# Core_h750vb.net
KiCad netlist of a schematic drawn in Altium Designer
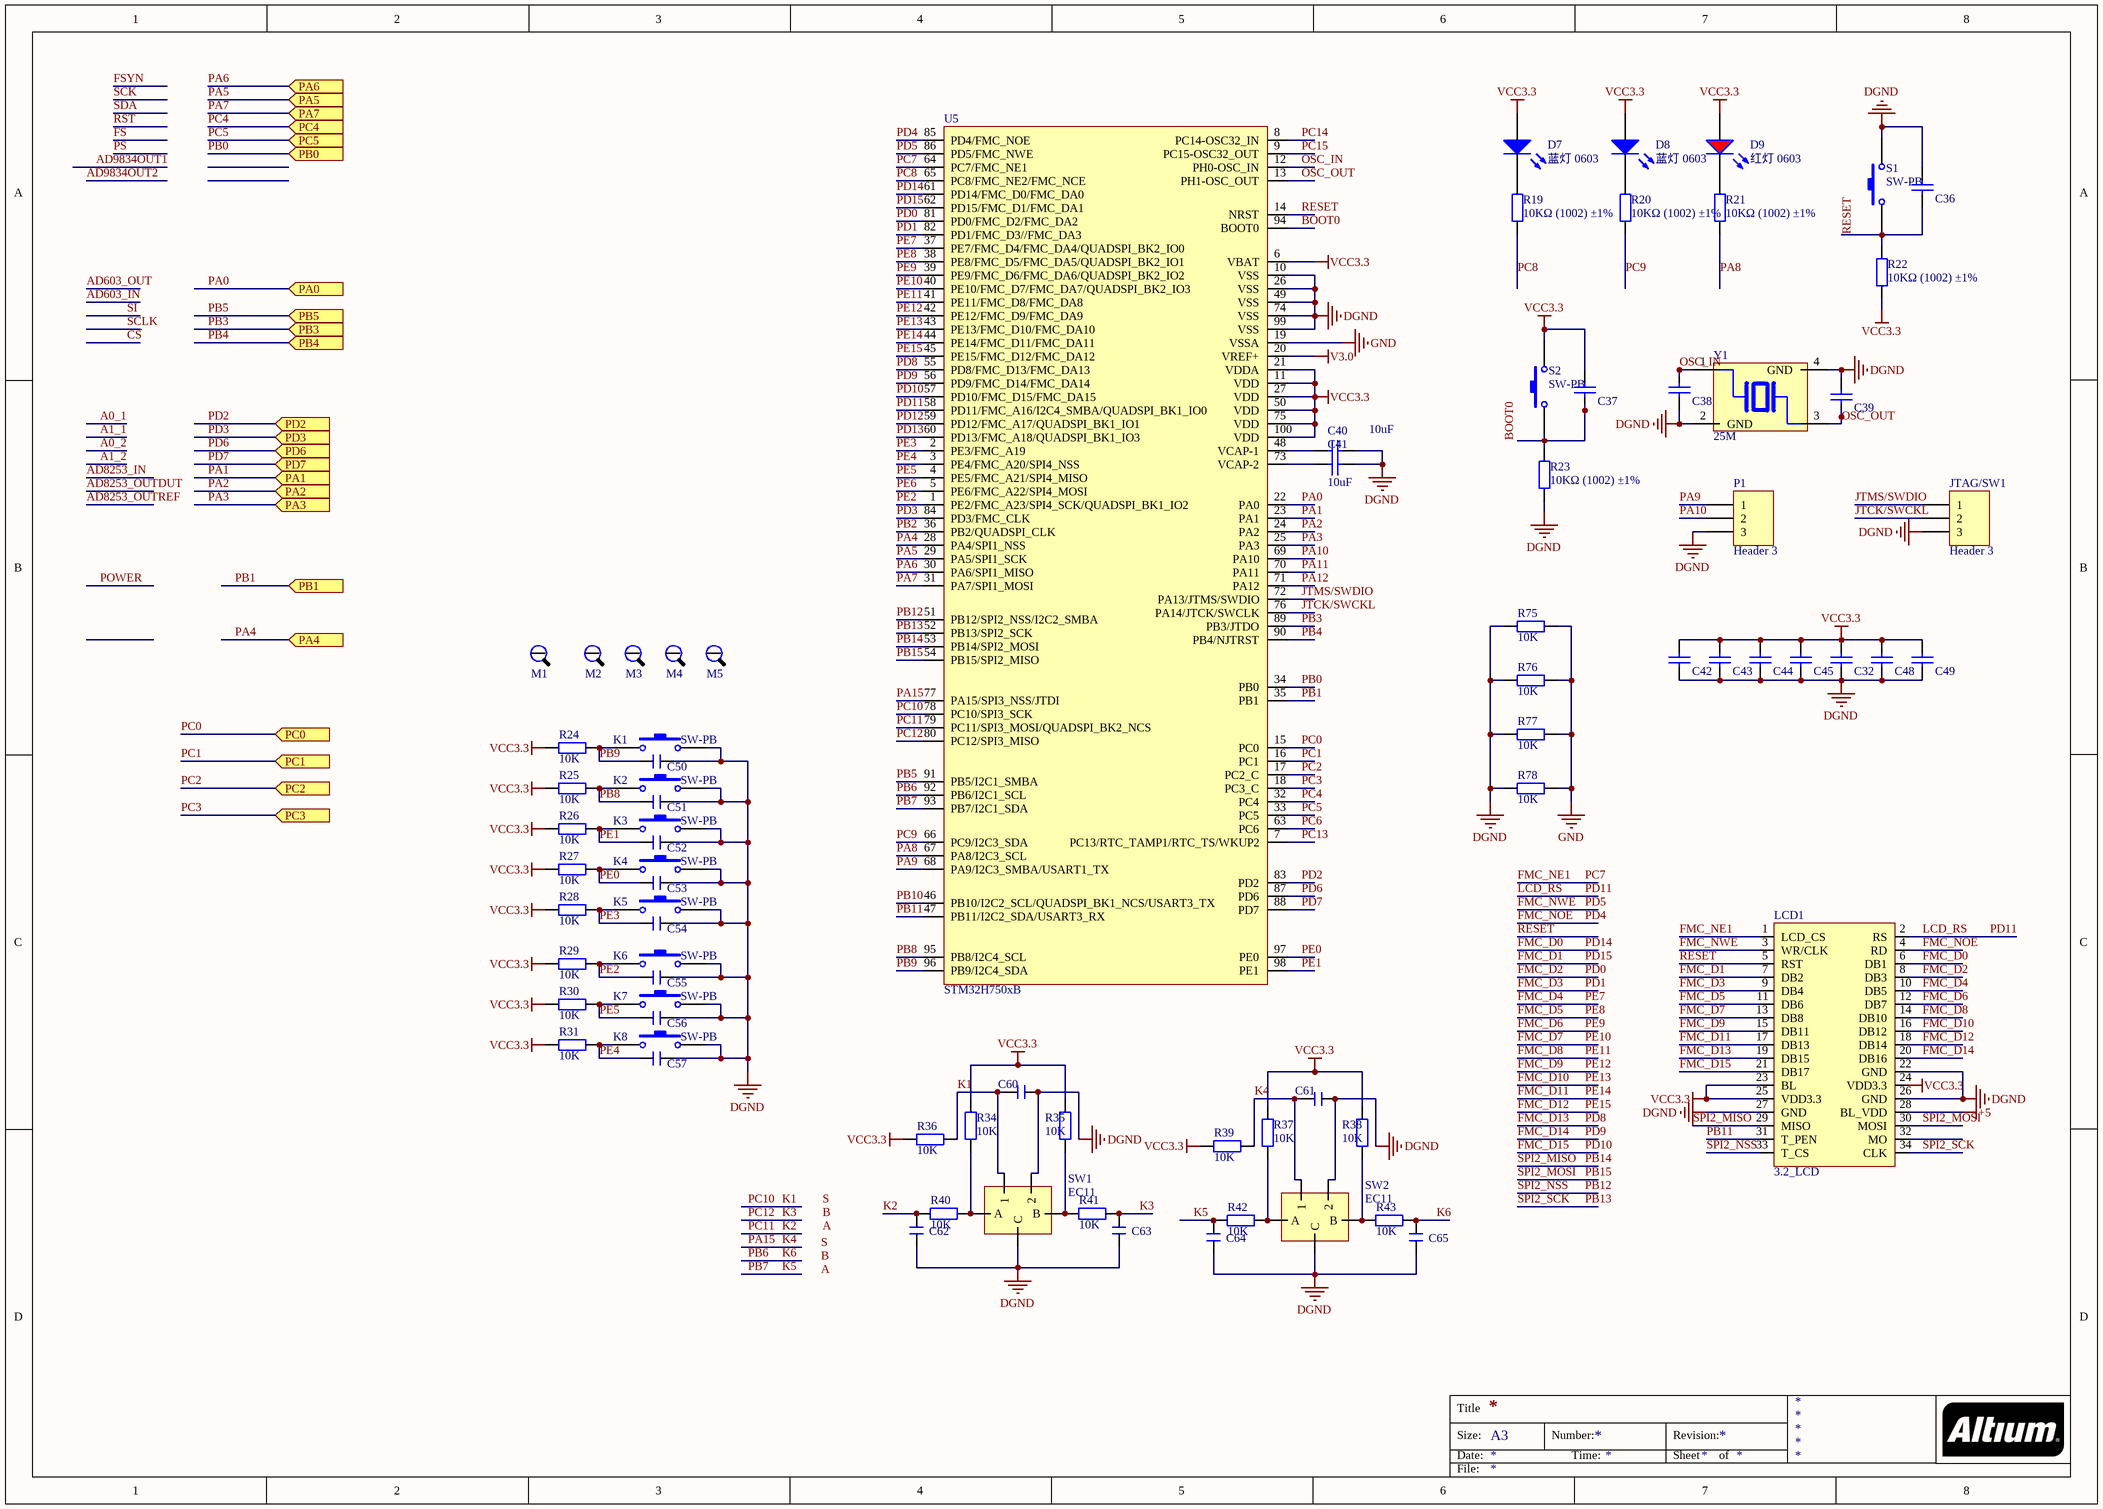
[diagram p0: Core_h750vb.SchDoc]

(export (version "E")
  (design (tool "Eeschema 10.0.6"))
  (components
    (comp (ref "C32")
      (value "100nF (104) 10% 50V")
      (footprint "0603_C")
      (description "贴片电容")
      (libsource (lib "JLC") (part "0603 100nF (104) 10% 50V"))
    )
    (comp (ref "C36")
      (value "100nF (104) 10% 50V")
      (footprint "0603_C")
      (description "贴片电容")
      (libsource (lib "JLC") (part "0603 100nF (104) 10% 50V"))
    )
    (comp (ref "C37")
      (value "100nF (104) 10% 50V")
      (footprint "0603_C")
      (description "贴片电容")
      (libsource (lib "JLC") (part "0603 100nF (104) 10% 50V"))
    )
    (comp (ref "C38")
      (value "100nF (104) 10% 50V")
      (footprint "0603_C")
      (description "贴片电容")
      (libsource (lib "JLC") (part "0603 100nF (104) 10% 50V"))
    )
    (comp (ref "C39")
      (value "100nF (104) 10% 50V")
      (footprint "0603_C")
      (description "贴片电容")
      (libsource (lib "JLC") (part "0603 100nF (104) 10% 50V"))
    )
    (comp (ref "C40")
      (value "10uF")
      (footprint "0603_C")
      (description "贴片电容")
      (libsource (lib "JLC") (part "0603 10uF (106) 10% 10V"))
    )
    (comp (ref "C41")
      (value "10uF")
      (footprint "0603_C")
      (description "贴片电容")
      (libsource (lib "JLC") (part "0603 10uF (106) 10% 10V"))
    )
    (comp (ref "C42")
      (value "100nF (104) 10% 50V")
      (footprint "0603_C")
      (description "贴片电容")
      (libsource (lib "JLC") (part "0603 100nF (104) 10% 50V"))
    )
    (comp (ref "C43")
      (value "100nF (104) 10% 50V")
      (footprint "0603_C")
      (description "贴片电容")
      (libsource (lib "JLC") (part "0603 100nF (104) 10% 50V"))
    )
    (comp (ref "C44")
      (value "100nF (104) 10% 50V")
      (footprint "0603_C")
      (description "贴片电容")
      (libsource (lib "JLC") (part "0603 100nF (104) 10% 50V"))
    )
    (comp (ref "C45")
      (value "100nF (104) 10% 50V")
      (footprint "0603_C")
      (description "贴片电容")
      (libsource (lib "JLC") (part "0603 100nF (104) 10% 50V"))
    )
    (comp (ref "C48")
      (value "100nF (104) 10% 50V")
      (footprint "0603_C")
      (description "贴片电容")
      (libsource (lib "JLC") (part "0603 100nF (104) 10% 50V"))
    )
    (comp (ref "C49")
      (value "100nF (104) 10% 50V")
      (footprint "0603_C")
      (description "贴片电容")
      (libsource (lib "JLC") (part "0603 100nF (104) 10% 50V"))
    )
    (comp (ref "C50")
      (value "104")
      (footprint "0603_C")
      (description "无极性贴片电容")
      (libsource (lib "各类封装") (part "C"))
    )
    (comp (ref "C51")
      (value "104")
      (footprint "0603_C")
      (description "无极性贴片电容")
      (libsource (lib "各类封装") (part "C"))
    )
    (comp (ref "C52")
      (value "104")
      (footprint "0603_C")
      (description "无极性贴片电容")
      (libsource (lib "各类封装") (part "C"))
    )
    (comp (ref "C53")
      (value "104")
      (footprint "0603_C")
      (description "无极性贴片电容")
      (libsource (lib "各类封装") (part "C"))
    )
    (comp (ref "C54")
      (value "104")
      (footprint "0603_C")
      (description "无极性贴片电容")
      (libsource (lib "各类封装") (part "C"))
    )
    (comp (ref "C55")
      (value "104")
      (footprint "0603_C")
      (description "无极性贴片电容")
      (libsource (lib "各类封装") (part "C"))
    )
    (comp (ref "C56")
      (value "104")
      (footprint "0603_C")
      (description "无极性贴片电容")
      (libsource (lib "各类封装") (part "C"))
    )
    (comp (ref "C57")
      (value "104")
      (footprint "0603_C")
      (description "无极性贴片电容")
      (libsource (lib "各类封装") (part "C"))
    )
    (comp (ref "C60")
      (value "104")
      (footprint "0603_C")
      (description "无极性贴片电容")
      (libsource (lib "各类封装") (part "C"))
    )
    (comp (ref "C61")
      (value "104")
      (footprint "0603_C")
      (description "无极性贴片电容")
      (libsource (lib "各类封装") (part "C"))
    )
    (comp (ref "C62")
      (value "104")
      (footprint "0603_C")
      (description "无极性贴片电容")
      (libsource (lib "各类封装") (part "C"))
    )
    (comp (ref "C63")
      (value "104")
      (footprint "0603_C")
      (description "无极性贴片电容")
      (libsource (lib "各类封装") (part "C"))
    )
    (comp (ref "C64")
      (value "104")
      (footprint "0603_C")
      (description "无极性贴片电容")
      (libsource (lib "各类封装") (part "C"))
    )
    (comp (ref "C65")
      (value "104")
      (footprint "0603_C")
      (description "无极性贴片电容")
      (libsource (lib "各类封装") (part "C"))
    )
    (comp (ref "D7")
      (value "蓝灯 0603")
      (footprint "0603_LED_S1")
      (description "发光二极管")
      (libsource (lib "JLC") (part "0603 蓝灯"))
    )
    (comp (ref "D8")
      (value "蓝灯 0603")
      (footprint "0603_LED_S1")
      (description "发光二极管")
      (libsource (lib "JLC") (part "0603 蓝灯"))
    )
    (comp (ref "D9")
      (value "红灯 0603")
      (footprint "0603_LED_S1")
      (description "发光二极管")
      (libsource (lib "JLC") (part "0603 红灯"))
    )
    (comp (ref "JTAG/SW1")
      (value "Header 3")
      (footprint "HDR1X3")
      (description "Header, 3-Pin")
      (fields (field (name "PUBLISHER") "Altium Limited"))
      (libsource (lib "Miscellaneous Connectors") (part "Header 3"))
    )
    (comp (ref "K1")
      (value "SW-PB")
      (footprint "SW_PB2_A1")
      (description "微动开关")
      (fields (field (name "PUBLISHER") "Altium Limited"))
      (libsource (lib "主集成库") (part "SW-PB"))
    )
    (comp (ref "K2")
      (value "SW-PB")
      (footprint "SW_PB2_A1")
      (description "微动开关")
      (fields (field (name "PUBLISHER") "Altium Limited"))
      (libsource (lib "主集成库") (part "SW-PB"))
    )
    (comp (ref "K3")
      (value "SW-PB")
      (footprint "SW_PB2_A1")
      (description "微动开关")
      (fields (field (name "PUBLISHER") "Altium Limited"))
      (libsource (lib "主集成库") (part "SW-PB"))
    )
    (comp (ref "K4")
      (value "SW-PB")
      (footprint "SW_PB2_A1")
      (description "微动开关")
      (fields (field (name "PUBLISHER") "Altium Limited"))
      (libsource (lib "主集成库") (part "SW-PB"))
    )
    (comp (ref "K5")
      (value "SW-PB")
      (footprint "SW_PB2_A1")
      (description "微动开关")
      (fields (field (name "PUBLISHER") "Altium Limited"))
      (libsource (lib "主集成库") (part "SW-PB"))
    )
    (comp (ref "K6")
      (value "SW-PB")
      (footprint "SW_PB2_A1")
      (description "微动开关")
      (fields (field (name "PUBLISHER") "Altium Limited"))
      (libsource (lib "主集成库") (part "SW-PB"))
    )
    (comp (ref "K7")
      (value "SW-PB")
      (footprint "SW_PB2_A1")
      (description "微动开关")
      (fields (field (name "PUBLISHER") "Altium Limited"))
      (libsource (lib "主集成库") (part "SW-PB"))
    )
    (comp (ref "K8")
      (value "SW-PB")
      (footprint "SW_PB2_A1")
      (description "微动开关")
      (fields (field (name "PUBLISHER") "Altium Limited"))
      (libsource (lib "主集成库") (part "SW-PB"))
    )
    (comp (ref "LCD1") (value "3.2_LCD") (footprint "LCD_3.2") (libsource (lib "直流电源") (part "3.2_LCD")))
    (comp (ref "M1")
      (value "M3")
      (footprint "M3x10_L")
      (description "螺丝")
      (libsource (lib "Cooperation") (part "ELSE_M3_screw"))
    )
    (comp (ref "M2")
      (value "M3")
      (footprint "M3x10_L")
      (description "螺丝")
      (libsource (lib "Cooperation") (part "ELSE_M3_screw"))
    )
    (comp (ref "M3")
      (value "M3")
      (footprint "M3x10_L")
      (description "螺丝")
      (libsource (lib "Cooperation") (part "ELSE_M3_screw"))
    )
    (comp (ref "M4")
      (value "M3")
      (footprint "M3x10_L")
      (description "螺丝")
      (libsource (lib "Cooperation") (part "ELSE_M3_screw"))
    )
    (comp (ref "M5")
      (value "M3")
      (footprint "M3x10_L")
      (description "螺丝")
      (libsource (lib "Cooperation") (part "ELSE_M3_screw"))
    )
    (comp (ref "P1")
      (value "Header 3")
      (footprint "HDR1X3")
      (description "Header, 3-Pin")
      (fields (field (name "PUBLISHER") "Altium Limited"))
      (libsource (lib "Miscellaneous Connectors") (part "Header 3"))
    )
    (comp (ref "R19")
      (value "10KΩ (1002) ±1%")
      (footprint "0603_R")
      (description "贴片电阻")
      (libsource (lib "JLC") (part "0603 10KΩ (1002) 1%"))
    )
    (comp (ref "R20")
      (value "10KΩ (1002) ±1%")
      (footprint "0603_R")
      (description "贴片电阻")
      (libsource (lib "JLC") (part "0603 10KΩ (1002) 1%"))
    )
    (comp (ref "R21")
      (value "10KΩ (1002) ±1%")
      (footprint "0603_R")
      (description "贴片电阻")
      (libsource (lib "JLC") (part "0603 10KΩ (1002) 1%"))
    )
    (comp (ref "R22")
      (value "10KΩ (1002) ±1%")
      (footprint "0603_R")
      (description "贴片电阻")
      (libsource (lib "JLC") (part "0603 10KΩ (1002) 1%"))
    )
    (comp (ref "R23")
      (value "10KΩ (1002) ±1%")
      (footprint "0603_R")
      (description "贴片电阻")
      (libsource (lib "JLC") (part "0603 10KΩ (1002) 1%"))
    )
    (comp (ref "R24")
      (value "10K")
      (footprint "0603-1")
      (description "贴片电阻")
      (fields (field (name "PUBLISHER") "Altium Limited"))
      (libsource (lib "") (part "Res1_1"))
    )
    (comp (ref "R25")
      (value "10K")
      (footprint "0603-1")
      (description "贴片电阻")
      (fields (field (name "PUBLISHER") "Altium Limited"))
      (libsource (lib "") (part "Res1_1"))
    )
    (comp (ref "R26")
      (value "10K")
      (footprint "0603-1")
      (description "贴片电阻")
      (fields (field (name "PUBLISHER") "Altium Limited"))
      (libsource (lib "") (part "Res1_1"))
    )
    (comp (ref "R27")
      (value "10K")
      (footprint "0603-1")
      (description "贴片电阻")
      (fields (field (name "PUBLISHER") "Altium Limited"))
      (libsource (lib "") (part "Res1_1"))
    )
    (comp (ref "R28")
      (value "10K")
      (footprint "0603-1")
      (description "贴片电阻")
      (fields (field (name "PUBLISHER") "Altium Limited"))
      (libsource (lib "") (part "Res1_1"))
    )
    (comp (ref "R29")
      (value "10K")
      (footprint "0603-1")
      (description "贴片电阻")
      (fields (field (name "PUBLISHER") "Altium Limited"))
      (libsource (lib "") (part "Res1_1"))
    )
    (comp (ref "R30")
      (value "10K")
      (footprint "0603-1")
      (description "贴片电阻")
      (fields (field (name "PUBLISHER") "Altium Limited"))
      (libsource (lib "") (part "Res1_1"))
    )
    (comp (ref "R31")
      (value "10K")
      (footprint "0603-1")
      (description "贴片电阻")
      (fields (field (name "PUBLISHER") "Altium Limited"))
      (libsource (lib "") (part "Res1_1"))
    )
    (comp (ref "R34")
      (value "10K")
      (footprint "0603-1")
      (description "贴片电阻")
      (fields (field (name "PUBLISHER") "Altium Limited"))
      (libsource (lib "主集成库") (part "Res1"))
    )
    (comp (ref "R35")
      (value "10K")
      (footprint "0603-1")
      (description "贴片电阻")
      (fields (field (name "PUBLISHER") "Altium Limited"))
      (libsource (lib "主集成库") (part "Res1"))
    )
    (comp (ref "R36")
      (value "10K")
      (footprint "0603-1")
      (description "贴片电阻")
      (fields (field (name "PUBLISHER") "Altium Limited"))
      (libsource (lib "") (part "Res1_2"))
    )
    (comp (ref "R37")
      (value "10K")
      (footprint "0603-1")
      (description "贴片电阻")
      (fields (field (name "PUBLISHER") "Altium Limited"))
      (libsource (lib "主集成库") (part "Res1"))
    )
    (comp (ref "R38")
      (value "10K")
      (footprint "0603-1")
      (description "贴片电阻")
      (fields (field (name "PUBLISHER") "Altium Limited"))
      (libsource (lib "主集成库") (part "Res1"))
    )
    (comp (ref "R39")
      (value "10K")
      (footprint "0603-1")
      (description "贴片电阻")
      (fields (field (name "PUBLISHER") "Altium Limited"))
      (libsource (lib "") (part "Res1_2"))
    )
    (comp (ref "R40")
      (value "10K")
      (footprint "0603-1")
      (description "贴片电阻")
      (fields (field (name "PUBLISHER") "Altium Limited"))
      (libsource (lib "") (part "Res1_2"))
    )
    (comp (ref "R41")
      (value "10K")
      (footprint "0603-1")
      (description "贴片电阻")
      (fields (field (name "PUBLISHER") "Altium Limited"))
      (libsource (lib "") (part "Res1_2"))
    )
    (comp (ref "R42")
      (value "10K")
      (footprint "0603-1")
      (description "贴片电阻")
      (fields (field (name "PUBLISHER") "Altium Limited"))
      (libsource (lib "") (part "Res1_2"))
    )
    (comp (ref "R43")
      (value "10K")
      (footprint "0603-1")
      (description "贴片电阻")
      (fields (field (name "PUBLISHER") "Altium Limited"))
      (libsource (lib "") (part "Res1_2"))
    )
    (comp (ref "R75")
      (value "10K")
      (footprint "0603-1")
      (description "贴片电阻")
      (fields (field (name "PUBLISHER") "Altium Limited"))
      (libsource (lib "") (part "Res1_1"))
    )
    (comp (ref "R76")
      (value "10K")
      (footprint "0603-1")
      (description "贴片电阻")
      (fields (field (name "PUBLISHER") "Altium Limited"))
      (libsource (lib "") (part "Res1_1"))
    )
    (comp (ref "R77")
      (value "10K")
      (footprint "0603-1")
      (description "贴片电阻")
      (fields (field (name "PUBLISHER") "Altium Limited"))
      (libsource (lib "") (part "Res1_1"))
    )
    (comp (ref "R78")
      (value "10K")
      (footprint "0603-1")
      (description "贴片电阻")
      (fields (field (name "PUBLISHER") "Altium Limited"))
      (libsource (lib "") (part "Res1_1"))
    )
    (comp (ref "S1")
      (value "SW-PB")
      (footprint "SW_PB2_A1")
      (description "微动开关")
      (fields (field (name "PUBLISHER") "Altium Limited"))
      (libsource (lib "主集成库") (part "SW-PB"))
    )
    (comp (ref "S2")
      (value "SW-PB")
      (footprint "SW_PB2_A1")
      (description "微动开关")
      (fields (field (name "PUBLISHER") "Altium Limited"))
      (libsource (lib "主集成库") (part "SW-PB"))
    )
    (comp (ref "SW1")
      (value "EC11")
      (footprint "EC11")
      (libsource (lib "Cooperation") (part "SWTICH_EC11_ENCODER"))
    )
    (comp (ref "SW2")
      (value "EC11")
      (footprint "EC11")
      (libsource (lib "Cooperation") (part "SWTICH_EC11_ENCODER"))
    )
    (comp (ref "U5")
      (value "STM32H750xB")
      (footprint "TQFP100_M")
      (libsource (lib "Cooperation") (part "IC_STM32H750xB"))
    )
    (comp (ref "Y1")
      (value "25M")
      (footprint "OSC 3225-4P")
      (fields (field (name "Comment") "CRYSTAL"))
      (libsource (lib "Cooperation") (part "CRYSTAL_晶振25M_3225"))
    )
  )
  (nets
    (net (code "1") (name "+5") (class "Default")
      (node (ref "LCD1") (pin "28") (pinfunction "BL_VDD_28") (pintype "passive"))
    )
    (net (code "15") (name "/BOOT0") (class "Default")
      (node (ref "C37") (pin "2") (pinfunction "2_2") (pintype "passive"))
      (node (ref "R23") (pin "2") (pinfunction "2_2") (pintype "passive"))
      (node (ref "S2") (pin "1") (pinfunction "1_1") (pintype "passive"))
      (node (ref "U5") (pin "94") (pinfunction "BOOT0_94") (pintype "passive"))
    )
    (net (code "16") (name "/FMC_D0") (class "Default")
      (node (ref "LCD1") (pin "6") (pinfunction "DB1_6") (pintype "passive"))
      (node (ref "U5") (pin "61") (pinfunction "PD14/FMC_D0/FMC_DA0_61") (pintype "passive"))
    )
    (net (code "17") (name "/FMC_D1") (class "Default")
      (node (ref "LCD1") (pin "7") (pinfunction "DB2_7") (pintype "passive"))
      (node (ref "U5") (pin "62") (pinfunction "PD15/FMC_D1/FMC_DA1_62") (pintype "passive"))
    )
    (net (code "18") (name "/FMC_D2") (class "Default")
      (node (ref "LCD1") (pin "8") (pinfunction "DB3_8") (pintype "passive"))
      (node (ref "U5") (pin "81") (pinfunction "PD0/FMC_D2/FMC_DA2_81") (pintype "passive"))
    )
    (net (code "19") (name "/FMC_D3") (class "Default")
      (node (ref "LCD1") (pin "9") (pinfunction "DB4_9") (pintype "passive"))
      (node (ref "U5") (pin "82") (pinfunction "PD1/FMC_D3//FMC_DA3_82") (pintype "passive"))
    )
    (net (code "20") (name "/FMC_D4") (class "Default")
      (node (ref "LCD1") (pin "10") (pinfunction "DB5_10") (pintype "passive"))
      (node (ref "U5") (pin "37") (pinfunction "PE7/FMC_D4/FMC_DA4/QUADSPI_BK2_IO0_37") (pintype "passive"))
    )
    (net (code "21") (name "/FMC_D5") (class "Default")
      (node (ref "LCD1") (pin "11") (pinfunction "DB6_11") (pintype "passive"))
      (node (ref "U5") (pin "38") (pinfunction "PE8/FMC_D5/FMC_DA5/QUADSPI_BK2_IO1_38") (pintype "passive"))
    )
    (net (code "22") (name "/FMC_D6") (class "Default")
      (node (ref "LCD1") (pin "12") (pinfunction "DB7_12") (pintype "passive"))
      (node (ref "U5") (pin "39") (pinfunction "PE9/FMC_D6/FMC_DA6/QUADSPI_BK2_IO2_39") (pintype "passive"))
    )
    (net (code "23") (name "/FMC_D7") (class "Default")
      (node (ref "LCD1") (pin "13") (pinfunction "DB8_13") (pintype "passive"))
      (node (ref "U5") (pin "40") (pinfunction "PE10/FMC_D7/FMC_DA7/QUADSPI_BK2_IO3_40") (pintype "passive"))
    )
    (net (code "24") (name "/FMC_D8") (class "Default")
      (node (ref "LCD1") (pin "14") (pinfunction "DB10_14") (pintype "passive"))
      (node (ref "U5") (pin "41") (pinfunction "PE11/FMC_D8/FMC_DA8_41") (pintype "passive"))
    )
    (net (code "25") (name "/FMC_D9") (class "Default")
      (node (ref "LCD1") (pin "15") (pinfunction "DB11_15") (pintype "passive"))
      (node (ref "U5") (pin "42") (pinfunction "PE12/FMC_D9/FMC_DA9_42") (pintype "passive"))
    )
    (net (code "26") (name "/FMC_D10") (class "Default")
      (node (ref "LCD1") (pin "16") (pinfunction "DB12_16") (pintype "passive"))
      (node (ref "U5") (pin "43") (pinfunction "PE13/FMC_D10/FMC_DA10_43") (pintype "passive"))
    )
    (net (code "27") (name "/FMC_D11") (class "Default")
      (node (ref "LCD1") (pin "17") (pinfunction "DB13_17") (pintype "passive"))
      (node (ref "U5") (pin "44") (pinfunction "PE14/FMC_D11/FMC_DA11_44") (pintype "passive"))
    )
    (net (code "28") (name "/FMC_D12") (class "Default")
      (node (ref "LCD1") (pin "18") (pinfunction "DB14_18") (pintype "passive"))
      (node (ref "U5") (pin "45") (pinfunction "PE15/FMC_D12/FMC_DA12_45") (pintype "passive"))
    )
    (net (code "29") (name "/FMC_D13") (class "Default")
      (node (ref "LCD1") (pin "19") (pinfunction "DB15_19") (pintype "passive"))
      (node (ref "U5") (pin "55") (pinfunction "PD8/FMC_D13/FMC_DA13_55") (pintype "passive"))
    )
    (net (code "30") (name "/FMC_D14") (class "Default")
      (node (ref "LCD1") (pin "20") (pinfunction "DB16_20") (pintype "passive"))
      (node (ref "U5") (pin "56") (pinfunction "PD9/FMC_D14/FMC_DA14_56") (pintype "passive"))
    )
    (net (code "31") (name "/FMC_D15") (class "Default")
      (node (ref "LCD1") (pin "21") (pinfunction "DB17_21") (pintype "passive"))
      (node (ref "U5") (pin "57") (pinfunction "PD10/FMC_D15/FMC_DA15_57") (pintype "passive"))
    )
    (net (code "32") (name "/FMC_NE1") (class "Default")
      (node (ref "LCD1") (pin "1") (pinfunction "LCD_CS_1") (pintype "passive"))
      (node (ref "U5") (pin "64") (pinfunction "PC7/FMC_NE1_64") (pintype "passive"))
    )
    (net (code "33") (name "/FMC_NOE") (class "Default")
      (node (ref "LCD1") (pin "4") (pinfunction "RD_4") (pintype "passive"))
      (node (ref "U5") (pin "85") (pinfunction "PD4/FMC_NOE_85") (pintype "passive"))
    )
    (net (code "34") (name "/FMC_NWE") (class "Default")
      (node (ref "LCD1") (pin "3") (pinfunction "WR/CLK_3") (pintype "passive"))
      (node (ref "U5") (pin "86") (pinfunction "PD5/FMC_NWE_86") (pintype "passive"))
    )
    (net (code "37") (name "/JTCK{slash}SWCKL") (class "Default")
      (node (ref "JTAG/SW1") (pin "2") (pinfunction "2_2") (pintype "passive"))
      (node (ref "U5") (pin "76") (pinfunction "PA14/JTCK/SWCLK_76") (pintype "passive"))
    )
    (net (code "38") (name "/JTMS{slash}SWDIO") (class "Default")
      (node (ref "JTAG/SW1") (pin "1") (pinfunction "1_1") (pintype "passive"))
      (node (ref "U5") (pin "72") (pinfunction "PA13/JTMS/SWDIO_72") (pintype "passive"))
    )
    (net (code "39") (name "/K1") (class "Default")
      (node (ref "C60") (pin "2") (pinfunction "2_2") (pintype "passive"))
      (node (ref "R36") (pin "2") (pinfunction "2_2") (pintype "passive"))
      (node (ref "SW1") (pin "1") (pinfunction "1_1") (pintype "passive"))
      (node (ref "U5") (pin "78") (pinfunction "PC10/SPI3_SCK_78") (pintype "passive"))
    )
    (net (code "40") (name "/K2") (class "Default")
      (node (ref "C62") (pin "1") (pinfunction "1_1") (pintype "passive"))
      (node (ref "R40") (pin "1") (pinfunction "1_1") (pintype "passive"))
      (node (ref "U5") (pin "79") (pinfunction "PC11/SPI3_MOSI/QUADSPI_BK2_NCS_79") (pintype "passive"))
    )
    (net (code "41") (name "/K3") (class "Default")
      (node (ref "C63") (pin "1") (pinfunction "1_1") (pintype "passive"))
      (node (ref "R41") (pin "2") (pinfunction "2_2") (pintype "passive"))
      (node (ref "U5") (pin "80") (pinfunction "PC12/SPI3_MISO_80") (pintype "passive"))
    )
    (net (code "42") (name "/K4") (class "Default")
      (node (ref "C61") (pin "2") (pinfunction "2_2") (pintype "passive"))
      (node (ref "R39") (pin "2") (pinfunction "2_2") (pintype "passive"))
      (node (ref "SW2") (pin "1") (pinfunction "1_1") (pintype "passive"))
      (node (ref "U5") (pin "77") (pinfunction "PA15/SPI3_NSS/JTDI_77") (pintype "passive"))
    )
    (net (code "43") (name "/K5") (class "Default")
      (node (ref "C64") (pin "1") (pinfunction "1_1") (pintype "passive"))
      (node (ref "R42") (pin "1") (pinfunction "1_1") (pintype "passive"))
      (node (ref "U5") (pin "93") (pinfunction "PB7/I2C1_SDA_93") (pintype "passive"))
    )
    (net (code "44") (name "/K6") (class "Default")
      (node (ref "C65") (pin "1") (pinfunction "1_1") (pintype "passive"))
      (node (ref "R43") (pin "2") (pinfunction "2_2") (pintype "passive"))
      (node (ref "U5") (pin "92") (pinfunction "PB6/I2C1_SCL_92") (pintype "passive"))
    )
    (net (code "45") (name "/LCD_RS") (class "Default")
      (node (ref "LCD1") (pin "2") (pinfunction "RS_2") (pintype "passive"))
      (node (ref "U5") (pin "58") (pinfunction "PD11/FMC_A16/I2C4_SMBA/QUADSPI_BK1_IO0_58") (pintype "passive"))
    )
    (net (code "46") (name "/OSC_IN") (class "Default")
      (node (ref "C38") (pin "1") (pinfunction "1_1") (pintype "passive"))
      (node (ref "U5") (pin "12") (pinfunction "PH0-OSC_IN_12") (pintype "passive"))
      (node (ref "Y1") (pin "1") (pinfunction "1_1") (pintype "passive"))
    )
    (net (code "47") (name "/OSC_OUT") (class "Default")
      (node (ref "C39") (pin "2") (pinfunction "2_2") (pintype "passive"))
      (node (ref "U5") (pin "13") (pinfunction "PH1-OSC_OUT_13") (pintype "passive"))
      (node (ref "Y1") (pin "3") (pinfunction "3_3") (pintype "passive"))
    )
    (net (code "48") (name "/PA0") (class "Default")
      (node (ref "U5") (pin "22") (pinfunction "PA0_22") (pintype "passive"))
    )
    (net (code "49") (name "/PA1") (class "Default")
      (node (ref "U5") (pin "23") (pinfunction "PA1_23") (pintype "passive"))
    )
    (net (code "50") (name "/PA2") (class "Default")
      (node (ref "U5") (pin "24") (pinfunction "PA2_24") (pintype "passive"))
    )
    (net (code "51") (name "/PA3") (class "Default")
      (node (ref "U5") (pin "25") (pinfunction "PA3_25") (pintype "passive"))
    )
    (net (code "52") (name "/PA4") (class "Default")
      (node (ref "U5") (pin "28") (pinfunction "PA4/SPI1_NSS_28") (pintype "passive"))
    )
    (net (code "53") (name "/PA5") (class "Default")
      (node (ref "U5") (pin "29") (pinfunction "PA5/SPI1_SCK_29") (pintype "passive"))
    )
    (net (code "54") (name "/PA6") (class "Default")
      (node (ref "U5") (pin "30") (pinfunction "PA6/SPI1_MISO_30") (pintype "passive"))
    )
    (net (code "55") (name "/PA7") (class "Default")
      (node (ref "U5") (pin "31") (pinfunction "PA7/SPI1_MOSI_31") (pintype "passive"))
    )
    (net (code "56") (name "/PA8") (class "Default")
      (node (ref "R21") (pin "1") (pinfunction "1_1") (pintype "passive"))
      (node (ref "U5") (pin "67") (pinfunction "PA8/I2C3_SCL_67") (pintype "passive"))
    )
    (net (code "57") (name "/PA9") (class "Default")
      (node (ref "P1") (pin "1") (pinfunction "1_1") (pintype "passive"))
      (node (ref "U5") (pin "68") (pinfunction "PA9/I2C3_SMBA/USART1_TX_68") (pintype "passive"))
    )
    (net (code "58") (name "/PA10") (class "Default")
      (node (ref "P1") (pin "2") (pinfunction "2_2") (pintype "passive"))
      (node (ref "U5") (pin "69") (pinfunction "PA10_69") (pintype "passive"))
    )
    (net (code "59") (name "/PA11") (class "Default")
      (node (ref "U5") (pin "70") (pinfunction "PA11_70") (pintype "passive"))
    )
    (net (code "60") (name "/PA12") (class "Default")
      (node (ref "U5") (pin "71") (pinfunction "PA12_71") (pintype "passive"))
    )
    (net (code "61") (name "/PB0") (class "Default")
      (node (ref "U5") (pin "34") (pinfunction "PB0_34") (pintype "passive"))
    )
    (net (code "62") (name "/PB1") (class "Default")
      (node (ref "U5") (pin "35") (pinfunction "PB1_35") (pintype "passive"))
    )
    (net (code "63") (name "/PB2") (class "Default")
      (node (ref "U5") (pin "36") (pinfunction "PB2/QUADSPI_CLK_36") (pintype "passive"))
    )
    (net (code "64") (name "/PB3") (class "Default")
      (node (ref "U5") (pin "89") (pinfunction "PB3/JTDO_89") (pintype "passive"))
    )
    (net (code "65") (name "/PB4") (class "Default")
      (node (ref "U5") (pin "90") (pinfunction "PB4/NJTRST_90") (pintype "passive"))
    )
    (net (code "66") (name "/PB5") (class "Default")
      (node (ref "U5") (pin "91") (pinfunction "PB5/I2C1_SMBA_91") (pintype "passive"))
    )
    (net (code "67") (name "/PB8") (class "Default")
      (node (ref "C51") (pin "1") (pinfunction "1_1") (pintype "passive"))
      (node (ref "K2") (pin "1") (pinfunction "1_1") (pintype "passive"))
      (node (ref "R25") (pin "1") (pinfunction "1_1") (pintype "passive"))
      (node (ref "U5") (pin "95") (pinfunction "PB8/I2C4_SCL_95") (pintype "passive"))
    )
    (net (code "68") (name "/PB9") (class "Default")
      (node (ref "C50") (pin "1") (pinfunction "1_1") (pintype "passive"))
      (node (ref "K1") (pin "1") (pinfunction "1_1") (pintype "passive"))
      (node (ref "R24") (pin "1") (pinfunction "1_1") (pintype "passive"))
      (node (ref "U5") (pin "96") (pinfunction "PB9/I2C4_SDA_96") (pintype "passive"))
    )
    (net (code "69") (name "/PB10") (class "Default")
      (node (ref "U5") (pin "46") (pinfunction "PB10/I2C2_SCL/QUADSPI_BK1_NCS/USART3_TX_46") (pintype "passive"))
    )
    (net (code "70") (name "/PB11") (class "Default")
      (node (ref "LCD1") (pin "31") (pinfunction "T_PEN_31") (pintype "passive"))
      (node (ref "U5") (pin "47") (pinfunction "PB11/I2C2_SDA/USART3_RX_47") (pintype "passive"))
    )
    (net (code "71") (name "/PB12") (class "Default")
      (node (ref "LCD1") (pin "33") (pinfunction "T_CS_33") (pintype "passive"))
      (node (ref "U5") (pin "51") (pinfunction "PB12/SPI2_NSS/I2C2_SMBA_51") (pintype "passive"))
    )
    (net (code "72") (name "/PB13") (class "Default")
      (node (ref "LCD1") (pin "34") (pinfunction "CLK_34") (pintype "passive"))
      (node (ref "U5") (pin "52") (pinfunction "PB13/SPI2_SCK_52") (pintype "passive"))
    )
    (net (code "73") (name "/PB14") (class "Default")
      (node (ref "LCD1") (pin "29") (pinfunction "MISO_29") (pintype "passive"))
      (node (ref "U5") (pin "53") (pinfunction "PB14/SPI2_MOSI_53") (pintype "passive"))
    )
    (net (code "74") (name "/PB15") (class "Default")
      (node (ref "LCD1") (pin "30") (pinfunction "MOSI_30") (pintype "passive"))
      (node (ref "U5") (pin "54") (pinfunction "PB15/SPI2_MISO_54") (pintype "passive"))
    )
    (net (code "75") (name "/PC0") (class "Default")
      (node (ref "U5") (pin "15") (pinfunction "PC0_15") (pintype "passive"))
    )
    (net (code "76") (name "/PC1") (class "Default")
      (node (ref "U5") (pin "16") (pinfunction "PC1_16") (pintype "passive"))
    )
    (net (code "77") (name "/PC2") (class "Default")
      (node (ref "U5") (pin "17") (pinfunction "PC2_C_17") (pintype "passive"))
    )
    (net (code "78") (name "/PC3") (class "Default")
      (node (ref "U5") (pin "18") (pinfunction "PC3_C_18") (pintype "passive"))
    )
    (net (code "79") (name "/PC4") (class "Default")
      (node (ref "U5") (pin "32") (pinfunction "PC4_32") (pintype "passive"))
    )
    (net (code "80") (name "/PC5") (class "Default")
      (node (ref "U5") (pin "33") (pinfunction "PC5_33") (pintype "passive"))
    )
    (net (code "81") (name "/PC6") (class "Default")
      (node (ref "U5") (pin "63") (pinfunction "PC6_63") (pintype "passive"))
    )
    (net (code "82") (name "/PC8") (class "Default")
      (node (ref "R19") (pin "1") (pinfunction "1_1") (pintype "passive"))
      (node (ref "U5") (pin "65") (pinfunction "PC8/FMC_NE2/FMC_NCE_65") (pintype "passive"))
    )
    (net (code "83") (name "/PC9") (class "Default")
      (node (ref "R20") (pin "1") (pinfunction "1_1") (pintype "passive"))
      (node (ref "U5") (pin "66") (pinfunction "PC9/I2C3_SDA_66") (pintype "passive"))
    )
    (net (code "84") (name "/PC13") (class "Default")
      (node (ref "U5") (pin "7") (pinfunction "PC13/RTC_TAMP1/RTC_TS/WKUP2_7") (pintype "passive"))
    )
    (net (code "85") (name "/PC14") (class "Default")
      (node (ref "U5") (pin "8") (pinfunction "PC14-OSC32_IN_8") (pintype "passive"))
    )
    (net (code "86") (name "/PC15") (class "Default")
      (node (ref "U5") (pin "9") (pinfunction "PC15-OSC32_OUT_9") (pintype "passive"))
    )
    (net (code "87") (name "/PD2") (class "Default")
      (node (ref "U5") (pin "83") (pinfunction "PD2_83") (pintype "passive"))
    )
    (net (code "88") (name "/PD3") (class "Default")
      (node (ref "U5") (pin "84") (pinfunction "PD3/FMC_CLK_84") (pintype "passive"))
    )
    (net (code "89") (name "/PD6") (class "Default")
      (node (ref "U5") (pin "87") (pinfunction "PD6_87") (pintype "passive"))
    )
    (net (code "90") (name "/PD7") (class "Default")
      (node (ref "U5") (pin "88") (pinfunction "PD7_88") (pintype "passive"))
    )
    (net (code "91") (name "/PD12") (class "Default")
      (node (ref "U5") (pin "59") (pinfunction "PD12/FMC_A17/QUADSPI_BK1_IO1_59") (pintype "passive"))
    )
    (net (code "92") (name "/PD13") (class "Default")
      (node (ref "U5") (pin "60") (pinfunction "PD13/FMC_A18/QUADSPI_BK1_IO3_60") (pintype "passive"))
    )
    (net (code "93") (name "/PE0") (class "Default")
      (node (ref "C53") (pin "1") (pinfunction "1_1") (pintype "passive"))
      (node (ref "K4") (pin "1") (pinfunction "1_1") (pintype "passive"))
      (node (ref "R27") (pin "1") (pinfunction "1_1") (pintype "passive"))
      (node (ref "U5") (pin "97") (pinfunction "PE0_97") (pintype "passive"))
    )
    (net (code "94") (name "/PE1") (class "Default")
      (node (ref "C52") (pin "1") (pinfunction "1_1") (pintype "passive"))
      (node (ref "K3") (pin "1") (pinfunction "1_1") (pintype "passive"))
      (node (ref "R26") (pin "1") (pinfunction "1_1") (pintype "passive"))
      (node (ref "U5") (pin "98") (pinfunction "PE1_98") (pintype "passive"))
    )
    (net (code "95") (name "/PE2") (class "Default")
      (node (ref "C55") (pin "1") (pinfunction "1_1") (pintype "passive"))
      (node (ref "K6") (pin "1") (pinfunction "1_1") (pintype "passive"))
      (node (ref "R29") (pin "1") (pinfunction "1_1") (pintype "passive"))
      (node (ref "U5") (pin "1") (pinfunction "PE2/FMC_A23/SPI4_SCK/QUADSPI_BK1_IO2_1") (pintype "passive"))
    )
    (net (code "96") (name "/PE3") (class "Default")
      (node (ref "C54") (pin "1") (pinfunction "1_1") (pintype "passive"))
      (node (ref "K5") (pin "1") (pinfunction "1_1") (pintype "passive"))
      (node (ref "R28") (pin "1") (pinfunction "1_1") (pintype "passive"))
      (node (ref "U5") (pin "2") (pinfunction "PE3/FMC_A19_2") (pintype "passive"))
    )
    (net (code "97") (name "/PE4") (class "Default")
      (node (ref "C57") (pin "1") (pinfunction "1_1") (pintype "passive"))
      (node (ref "K8") (pin "1") (pinfunction "1_1") (pintype "passive"))
      (node (ref "R31") (pin "1") (pinfunction "1_1") (pintype "passive"))
      (node (ref "U5") (pin "3") (pinfunction "PE4/FMC_A20/SPI4_NSS_3") (pintype "passive"))
    )
    (net (code "98") (name "/PE5") (class "Default")
      (node (ref "C56") (pin "1") (pinfunction "1_1") (pintype "passive"))
      (node (ref "K7") (pin "1") (pinfunction "1_1") (pintype "passive"))
      (node (ref "R30") (pin "1") (pinfunction "1_1") (pintype "passive"))
      (node (ref "U5") (pin "4") (pinfunction "PE5/FMC_A21/SPI4_MISO_4") (pintype "passive"))
    )
    (net (code "99") (name "/PE6") (class "Default")
      (node (ref "U5") (pin "5") (pinfunction "PE6/FMC_A22/SPI4_MOSI_5") (pintype "passive"))
    )
    (net (code "102") (name "/RESET") (class "Default")
      (node (ref "C36") (pin "2") (pinfunction "2_2") (pintype "passive"))
      (node (ref "LCD1") (pin "5") (pinfunction "RST_5") (pintype "passive"))
      (node (ref "R22") (pin "2") (pinfunction "2_2") (pintype "passive"))
      (node (ref "S1") (pin "1") (pinfunction "1_1") (pintype "passive"))
      (node (ref "U5") (pin "14") (pinfunction "NRST_14") (pintype "passive"))
    )
    (net (code "110") (name "DGND") (class "Default")
      (node (ref "C32") (pin "2") (pinfunction "2_2") (pintype "passive"))
      (node (ref "C36") (pin "1") (pinfunction "1_1") (pintype "passive"))
      (node (ref "C38") (pin "2") (pinfunction "2_2") (pintype "passive"))
      (node (ref "C39") (pin "1") (pinfunction "1_1") (pintype "passive"))
      (node (ref "C40") (pin "1") (pinfunction "1_1") (pintype "passive"))
      (node (ref "C41") (pin "1") (pinfunction "1_1") (pintype "passive"))
      (node (ref "C42") (pin "2") (pinfunction "2_2") (pintype "passive"))
      (node (ref "C43") (pin "2") (pinfunction "2_2") (pintype "passive"))
      (node (ref "C44") (pin "2") (pinfunction "2_2") (pintype "passive"))
      (node (ref "C45") (pin "2") (pinfunction "2_2") (pintype "passive"))
      (node (ref "C48") (pin "2") (pinfunction "2_2") (pintype "passive"))
      (node (ref "C49") (pin "2") (pinfunction "2_2") (pintype "passive"))
      (node (ref "C50") (pin "2") (pinfunction "2_2") (pintype "passive"))
      (node (ref "C51") (pin "2") (pinfunction "2_2") (pintype "passive"))
      (node (ref "C52") (pin "2") (pinfunction "2_2") (pintype "passive"))
      (node (ref "C53") (pin "2") (pinfunction "2_2") (pintype "passive"))
      (node (ref "C54") (pin "2") (pinfunction "2_2") (pintype "passive"))
      (node (ref "C55") (pin "2") (pinfunction "2_2") (pintype "passive"))
      (node (ref "C56") (pin "2") (pinfunction "2_2") (pintype "passive"))
      (node (ref "C57") (pin "2") (pinfunction "2_2") (pintype "passive"))
      (node (ref "C60") (pin "1") (pinfunction "1_1") (pintype "passive"))
      (node (ref "C61") (pin "1") (pinfunction "1_1") (pintype "passive"))
      (node (ref "C62") (pin "2") (pinfunction "2_2") (pintype "passive"))
      (node (ref "C63") (pin "2") (pinfunction "2_2") (pintype "passive"))
      (node (ref "C64") (pin "2") (pinfunction "2_2") (pintype "passive"))
      (node (ref "C65") (pin "2") (pinfunction "2_2") (pintype "passive"))
      (node (ref "JTAG/SW1") (pin "3") (pinfunction "3_3") (pintype "passive"))
      (node (ref "K1") (pin "2") (pinfunction "2_2") (pintype "passive"))
      (node (ref "K2") (pin "2") (pinfunction "2_2") (pintype "passive"))
      (node (ref "K3") (pin "2") (pinfunction "2_2") (pintype "passive"))
      (node (ref "K4") (pin "2") (pinfunction "2_2") (pintype "passive"))
      (node (ref "K5") (pin "2") (pinfunction "2_2") (pintype "passive"))
      (node (ref "K6") (pin "2") (pinfunction "2_2") (pintype "passive"))
      (node (ref "K7") (pin "2") (pinfunction "2_2") (pintype "passive"))
      (node (ref "K8") (pin "2") (pinfunction "2_2") (pintype "passive"))
      (node (ref "LCD1") (pin "22") (pinfunction "GND_22") (pintype "passive"))
      (node (ref "LCD1") (pin "26") (pinfunction "GND_26") (pintype "passive"))
      (node (ref "LCD1") (pin "27") (pinfunction "GND_27") (pintype "passive"))
      (node (ref "P1") (pin "3") (pinfunction "3_3") (pintype "passive"))
      (node (ref "R23") (pin "1") (pinfunction "1_1") (pintype "passive"))
      (node (ref "R75") (pin "2") (pinfunction "2_2") (pintype "passive"))
      (node (ref "R76") (pin "2") (pinfunction "2_2") (pintype "passive"))
      (node (ref "R77") (pin "2") (pinfunction "2_2") (pintype "passive"))
      (node (ref "R78") (pin "2") (pinfunction "2_2") (pintype "passive"))
      (node (ref "S1") (pin "2") (pinfunction "2_2") (pintype "passive"))
      (node (ref "SW1") (pin "2") (pinfunction "2_2") (pintype "passive"))
      (node (ref "SW1") (pin "C") (pinfunction "C_C") (pintype "passive"))
      (node (ref "SW2") (pin "2") (pinfunction "2_2") (pintype "passive"))
      (node (ref "SW2") (pin "C") (pinfunction "C_C") (pintype "passive"))
      (node (ref "U5") (pin "10") (pinfunction "VSS_10") (pintype "passive"))
      (node (ref "U5") (pin "26") (pinfunction "VSS_26") (pintype "passive"))
      (node (ref "U5") (pin "49") (pinfunction "VSS_49") (pintype "passive"))
      (node (ref "U5") (pin "74") (pinfunction "VSS_74") (pintype "passive"))
      (node (ref "U5") (pin "99") (pinfunction "VSS_99") (pintype "passive"))
      (node (ref "Y1") (pin "2") (pinfunction "GND_2") (pintype "passive"))
      (node (ref "Y1") (pin "4") (pinfunction "GND_4") (pintype "passive"))
    )
    (net (code "111") (name "GND") (class "Default")
      (node (ref "R75") (pin "1") (pinfunction "1_1") (pintype "passive"))
      (node (ref "R76") (pin "1") (pinfunction "1_1") (pintype "passive"))
      (node (ref "R77") (pin "1") (pinfunction "1_1") (pintype "passive"))
      (node (ref "R78") (pin "1") (pinfunction "1_1") (pintype "passive"))
      (node (ref "U5") (pin "19") (pinfunction "VSSA_19") (pintype "passive"))
    )
    (net (code "112") (name "Net-(D7-PadK)") (class "Default")
      (node (ref "D7") (pin "K") (pinfunction "K_K") (pintype "passive"))
      (node (ref "R19") (pin "2") (pinfunction "2_2") (pintype "passive"))
    )
    (net (code "113") (name "Net-(D8-PadK)") (class "Default")
      (node (ref "D8") (pin "K") (pinfunction "K_K") (pintype "passive"))
      (node (ref "R20") (pin "2") (pinfunction "2_2") (pintype "passive"))
    )
    (net (code "114") (name "Net-(D9-PadK)") (class "Default")
      (node (ref "D9") (pin "K") (pinfunction "K_K") (pintype "passive"))
      (node (ref "R21") (pin "2") (pinfunction "2_2") (pintype "passive"))
    )
    (net (code "115") (name "Net-(R34-Pad1)") (class "Default")
      (node (ref "R34") (pin "1") (pinfunction "1_1") (pintype "passive"))
      (node (ref "R40") (pin "2") (pinfunction "2_2") (pintype "passive"))
      (node (ref "SW1") (pin "A") (pinfunction "A_A") (pintype "passive"))
    )
    (net (code "116") (name "Net-(R35-Pad1)") (class "Default")
      (node (ref "R35") (pin "1") (pinfunction "1_1") (pintype "passive"))
      (node (ref "R41") (pin "1") (pinfunction "1_1") (pintype "passive"))
      (node (ref "SW1") (pin "B") (pinfunction "B_B") (pintype "passive"))
    )
    (net (code "117") (name "Net-(R37-Pad1)") (class "Default")
      (node (ref "R37") (pin "1") (pinfunction "1_1") (pintype "passive"))
      (node (ref "R42") (pin "2") (pinfunction "2_2") (pintype "passive"))
      (node (ref "SW2") (pin "A") (pinfunction "A_A") (pintype "passive"))
    )
    (net (code "118") (name "Net-(R38-Pad1)") (class "Default")
      (node (ref "R38") (pin "1") (pinfunction "1_1") (pintype "passive"))
      (node (ref "R43") (pin "1") (pinfunction "1_1") (pintype "passive"))
      (node (ref "SW2") (pin "B") (pinfunction "B_B") (pintype "passive"))
    )
    (net (code "119") (name "Net-(U5-VCAP-1)") (class "Default")
      (node (ref "C40") (pin "2") (pinfunction "2_2") (pintype "passive"))
      (node (ref "U5") (pin "48") (pinfunction "VCAP-1_48") (pintype "passive"))
    )
    (net (code "120") (name "Net-(U5-VCAP-2)") (class "Default")
      (node (ref "C41") (pin "2") (pinfunction "2_2") (pintype "passive"))
      (node (ref "U5") (pin "73") (pinfunction "VCAP-2_73") (pintype "passive"))
    )
    (net (code "121") (name "V3.0") (class "Default")
      (node (ref "U5") (pin "20") (pinfunction "VREF+_20") (pintype "passive"))
    )
    (net (code "122") (name "VCC3.3") (class "Default")
      (node (ref "C32") (pin "1") (pinfunction "1_1") (pintype "passive"))
      (node (ref "C37") (pin "1") (pinfunction "1_1") (pintype "passive"))
      (node (ref "C42") (pin "1") (pinfunction "1_1") (pintype "passive"))
      (node (ref "C43") (pin "1") (pinfunction "1_1") (pintype "passive"))
      (node (ref "C44") (pin "1") (pinfunction "1_1") (pintype "passive"))
      (node (ref "C45") (pin "1") (pinfunction "1_1") (pintype "passive"))
      (node (ref "C48") (pin "1") (pinfunction "1_1") (pintype "passive"))
      (node (ref "C49") (pin "1") (pinfunction "1_1") (pintype "passive"))
      (node (ref "D7") (pin "A") (pinfunction "A_A") (pintype "passive"))
      (node (ref "D8") (pin "A") (pinfunction "A_A") (pintype "passive"))
      (node (ref "D9") (pin "A") (pinfunction "A_A") (pintype "passive"))
      (node (ref "LCD1") (pin "23") (pinfunction "BL_23") (pintype "passive"))
      (node (ref "LCD1") (pin "24") (pinfunction "VDD3.3_24") (pintype "passive"))
      (node (ref "LCD1") (pin "25") (pinfunction "VDD3.3_25") (pintype "passive"))
      (node (ref "R22") (pin "1") (pinfunction "1_1") (pintype "passive"))
      (node (ref "R24") (pin "2") (pinfunction "2_2") (pintype "passive"))
      (node (ref "R25") (pin "2") (pinfunction "2_2") (pintype "passive"))
      (node (ref "R26") (pin "2") (pinfunction "2_2") (pintype "passive"))
      (node (ref "R27") (pin "2") (pinfunction "2_2") (pintype "passive"))
      (node (ref "R28") (pin "2") (pinfunction "2_2") (pintype "passive"))
      (node (ref "R29") (pin "2") (pinfunction "2_2") (pintype "passive"))
      (node (ref "R30") (pin "2") (pinfunction "2_2") (pintype "passive"))
      (node (ref "R31") (pin "2") (pinfunction "2_2") (pintype "passive"))
      (node (ref "R34") (pin "2") (pinfunction "2_2") (pintype "passive"))
      (node (ref "R35") (pin "2") (pinfunction "2_2") (pintype "passive"))
      (node (ref "R36") (pin "1") (pinfunction "1_1") (pintype "passive"))
      (node (ref "R37") (pin "2") (pinfunction "2_2") (pintype "passive"))
      (node (ref "R38") (pin "2") (pinfunction "2_2") (pintype "passive"))
      (node (ref "R39") (pin "1") (pinfunction "1_1") (pintype "passive"))
      (node (ref "S2") (pin "2") (pinfunction "2_2") (pintype "passive"))
      (node (ref "U5") (pin "100") (pinfunction "VDD_100") (pintype "passive"))
      (node (ref "U5") (pin "11") (pinfunction "VDD_11") (pintype "passive"))
      (node (ref "U5") (pin "21") (pinfunction "VDDA_21") (pintype "passive"))
      (node (ref "U5") (pin "27") (pinfunction "VDD_27") (pintype "passive"))
      (node (ref "U5") (pin "50") (pinfunction "VDD_50") (pintype "passive"))
      (node (ref "U5") (pin "6") (pinfunction "VBAT_6") (pintype "passive"))
      (node (ref "U5") (pin "75") (pinfunction "VDD_75") (pintype "passive"))
    )
    (net (code "123") (name "unconnected-(LCD1-MO-Pad32)") (class "Default")
      (node (ref "LCD1") (pin "32") (pinfunction "MO_32") (pintype "passive"))
    )
    (net (code "124") (name "unconnected-(M1-Pad1)") (class "Default")
      (node (ref "M1") (pin "1") (pinfunction "1_1") (pintype "passive"))
    )
    (net (code "125") (name "unconnected-(M2-Pad1)") (class "Default")
      (node (ref "M2") (pin "1") (pinfunction "1_1") (pintype "passive"))
    )
    (net (code "126") (name "unconnected-(M3-Pad1)") (class "Default")
      (node (ref "M3") (pin "1") (pinfunction "1_1") (pintype "passive"))
    )
    (net (code "127") (name "unconnected-(M4-Pad1)") (class "Default")
      (node (ref "M4") (pin "1") (pinfunction "1_1") (pintype "passive"))
    )
    (net (code "128") (name "unconnected-(M5-Pad1)") (class "Default")
      (node (ref "M5") (pin "1") (pinfunction "1_1") (pintype "passive"))
    )
  )
)
